# 04-Peripheral_Interface.net
KiCad netlist of a schematic drawn in Altium Designer
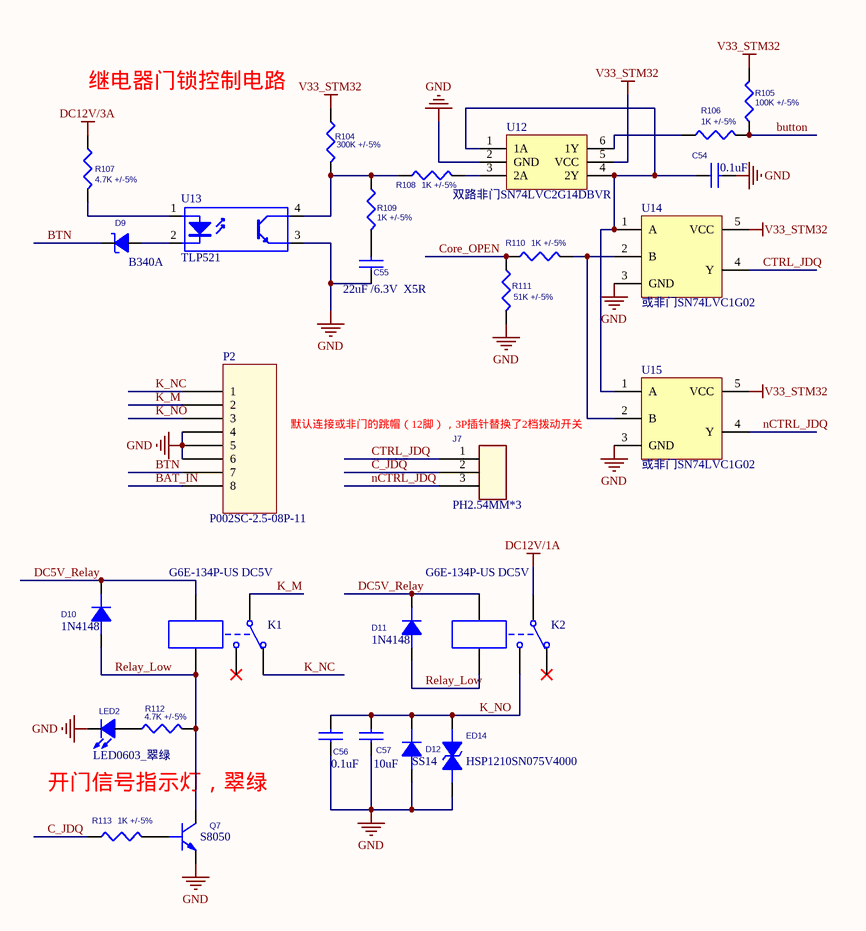
[diagram p0: 04-Peripheral Interface.SchDoc]

(export (version "E")
  (design (tool "Eeschema 10.0.6"))
  (components
    (comp (ref "C54")
      (value "0.1uF")
      (footprint "C0402")
      (description "表贴无极电容 0.1uF +10/-10% X7R")
      (libsource (lib "My_Library") (part "CAP"))
    )
    (comp (ref "C55")
      (value "22uF /6.3V  X5R")
      (footprint "C0805")
      (description "RoHS CHIP CAP 0.1uF +10/-10% X7R")
      (libsource (lib "My_Library") (part "CAP"))
    )
    (comp (ref "C56")
      (value "0.1uF")
      (footprint "C0402")
      (description "RoHS CHIP CAP 0.1uF +10/-10% X7R")
      (libsource (lib "My_Library") (part "CAP"))
    )
    (comp (ref "C57")
      (value "10uF")
      (footprint "C0603")
      (description "RoHS CHIP CAP 0.1uF +10/-10% X7R")
      (libsource (lib "My_Library") (part "CAP"))
    )
    (comp (ref "D9")
      (value "B340A")
      (footprint "DO-214AC/SMA")
      (description "RoHS 0.5A SURFACE MOUNT SCHOTTKY BARRIER RECTIFIER 1N5819")
      (libsource (lib "My_Library") (part "DIODE_Schottky-0"))
    )
    (comp (ref "D10")
      (value "1N4148")
      (footprint "SOD323")
      (description "RoHS 0.5A SURFACE MOUNT SCHOTTKY BARRIER RECTIFIER 1N5819")
      (libsource (lib "My_Library") (part "DIODE"))
    )
    (comp (ref "D11")
      (value "1N4148")
      (footprint "SOD323")
      (description "RoHS 0.5A SURFACE MOUNT SCHOTTKY BARRIER RECTIFIER 1N5819")
      (libsource (lib "My_Library") (part "DIODE"))
    )
    (comp (ref "D12")
      (value "SS14")
      (footprint "DO-214AA/SMB")
      (description "RoHS 0.5A SURFACE MOUNT SCHOTTKY BARRIER RECTIFIER 1N5819")
      (libsource (lib "My_Library") (part "DIODE"))
    )
    (comp (ref "ED14")
      (value "HSP1210SN075V4000")
      (footprint "ESD1210")
      (description "AEM科技（苏州）股份有限公司西南区成都办事处    销售主管：张莉  电话18030573868")
      (libsource (lib "My_Library") (part "ESD"))
    )
    (comp (ref "J7")
      (value "PH2.54MM*3")
      (footprint "CON3")
      (description "2.54mm单排插针，默认短接靠近或非门字样的1 2脚")
      (libsource (lib "My_Library") (part "CON3"))
    )
    (comp (ref "K1")
      (value "G6E-134P-US DC5V")
      (footprint "G6E134PUS")
      (description "https://item.taobao.com/item.htm?spm=a1z09.2.0.0.8b3ce33OERfgM&id=552384788811&_u=mb0qso78504")
      (fields (field (name "PUBLISHER") "Altium Limited"))
      (libsource (lib "My_Library") (part "Relay-SPDT"))
    )
    (comp (ref "K2")
      (value "G6E-134P-US DC5V")
      (footprint "G6E134PUS")
      (description "https://item.taobao.com/item.htm?spm=a1z09.2.0.0.8b3ce33OERfgM&id=552384788811&_u=mb0qso78504")
      (fields (field (name "PUBLISHER") "Altium Limited"))
      (libsource (lib "My_Library") (part "Relay-SPDT"))
    )
    (comp (ref "LED2")
      (value "LED0603_翠绿")
      (footprint "LED0603")
      (description "0603LED指示灯，颜色不同")
      (libsource (lib "My_Library") (part "LED"))
    )
    (comp (ref "P2")
      (value "P002SC-2.5-08P-11")
      (footprint "2EDGKD-2.5-8P")
      (description "门禁8P连接座，成都联益都电子有限公司，联系电话17780015645，邮箱lyconn107@163.com")
      (libsource (lib "My_Library") (part "2EDGKD-2.5-8P"))
    )
    (comp (ref "Q7") (value "S8050") (footprint "SOT23") (libsource (lib "My_Library") (part "NPN")))
    (comp (ref "R104") (value "300K +/-5%") (footprint "R0402") (libsource (lib "My_Library") (part "RES")))
    (comp (ref "R105") (value "100K +/-5%") (footprint "R0402") (libsource (lib "My_Library") (part "RES")))
    (comp (ref "R106") (value "1K +/-5%") (footprint "R0402") (libsource (lib "My_Library") (part "RES")))
    (comp (ref "R107") (value "4.7K +/-5%") (footprint "R0402") (libsource (lib "My_Library") (part "RES")))
    (comp (ref "R108") (value "1K +/-5%") (footprint "R0402") (libsource (lib "My_Library") (part "RES")))
    (comp (ref "R109") (value "1K +/-5%") (footprint "R0402") (libsource (lib "My_Library") (part "RES")))
    (comp (ref "R110") (value "1K +/-5%") (footprint "R0402") (libsource (lib "My_Library") (part "RES")))
    (comp (ref "R111") (value "51K +/-5%") (footprint "R0402") (libsource (lib "My_Library") (part "RES")))
    (comp (ref "R112") (value "4.7K +/-5%") (footprint "R0402") (libsource (lib "My_Library") (part "RES")))
    (comp (ref "R113") (value "1K +/-5%") (footprint "R0402") (libsource (lib "My_Library") (part "RES")))
    (comp (ref "U12")
      (value "双路非门SN74LVC2G14DBVR")
      (footprint "SOT23-6")
      (description "2路反相器    文晔集团    王忠凯，13823710380")
      (fields (field (name "DESIGNER") "Beyond@MXJ"))
      (libsource (lib "My_Library") (part "SN74LVC2G14DBVR"))
    )
    (comp (ref "U13")
      (value "TLP521")
      (footprint "SMD-4")
      (description "TLP521 SMD-4    安森美或者东芝品牌")
      (fields (field (name "DESIGNER") "BEYOND@MXJ"))
      (libsource (lib "My_Library") (part "TLP521"))
    )
    (comp (ref "U14")
      (value "或非门SN74LVC1G02")
      (footprint "SOT23-5")
      (description "单路 2 输入逻辑门    文晔集团    王忠凯，13823710380")
      (fields (field (name "DESIGNER") "Beyond@MXJ"))
      (libsource (lib "My_Library") (part "Single 2-input"))
    )
    (comp (ref "U15")
      (value "或非门SN74LVC1G02")
      (footprint "SOT23-5")
      (description "单路 2 输入逻辑门     文晔集团    王忠凯，13823710380")
      (fields (field (name "DESIGNER") "Beyond@MXJ"))
      (libsource (lib "My_Library") (part "Single 2-input"))
    )
  )
  (nets
    (net (code "1") (name "/BAT_IN") (class "Default")
      (node (ref "P2") (pin "8") (pinfunction "8_8") (pintype "passive"))
    )
    (net (code "2") (name "/BTN") (class "Default")
      (node (ref "D9") (pin "2") (pinfunction "K_2") (pintype "passive"))
      (node (ref "P2") (pin "7") (pinfunction "7_7") (pintype "passive"))
    )
    (net (code "3") (name "/CTRL_JDQ") (class "Default")
      (node (ref "J7") (pin "1") (pinfunction "1_1") (pintype "passive"))
      (node (ref "U14") (pin "4") (pinfunction "Y_4") (pintype "passive"))
    )
    (net (code "4") (name "/C_JDQ") (class "Default")
      (node (ref "J7") (pin "2") (pinfunction "2_2") (pintype "passive"))
      (node (ref "R113") (pin "1") (pinfunction "R1_1") (pintype "passive"))
    )
    (net (code "5") (name "/Core_OPEN") (class "Default")
      (node (ref "R110") (pin "1") (pinfunction "R1_1") (pintype "passive"))
      (node (ref "R111") (pin "1") (pinfunction "R1_1") (pintype "passive"))
    )
    (net (code "6") (name "/DC5V_Relay") (class "Default")
      (node (ref "D10") (pin "2") (pinfunction "K_2") (pintype "passive"))
      (node (ref "D11") (pin "2") (pinfunction "K_2") (pintype "passive"))
      (node (ref "K1") (pin "1") (pinfunction "1_1") (pintype "passive"))
      (node (ref "K2") (pin "1") (pinfunction "1_1") (pintype "passive"))
    )
    (net (code "7") (name "/K_M") (class "Default")
      (node (ref "K1") (pin "7") (pinfunction "7_7") (pintype "passive"))
      (node (ref "P2") (pin "2") (pinfunction "2_2") (pintype "passive"))
    )
    (net (code "8") (name "/K_NC") (class "Default")
      (node (ref "K1") (pin "10") (pinfunction "10_10") (pintype "passive"))
      (node (ref "P2") (pin "1") (pinfunction "1_1") (pintype "passive"))
    )
    (net (code "9") (name "/K_NO") (class "Default")
      (node (ref "C56") (pin "2") (pinfunction "2_2") (pintype "passive"))
      (node (ref "C57") (pin "2") (pinfunction "2_2") (pintype "passive"))
      (node (ref "D12") (pin "2") (pinfunction "K_2") (pintype "passive"))
      (node (ref "ED14") (pin "2") (pinfunction "2_2") (pintype "passive"))
      (node (ref "K2") (pin "12") (pinfunction "12_12") (pintype "passive"))
      (node (ref "P2") (pin "3") (pinfunction "3_3") (pintype "passive"))
    )
    (net (code "10") (name "/Relay_Low") (class "Default")
      (node (ref "D10") (pin "1") (pinfunction "A_1") (pintype "passive"))
      (node (ref "D11") (pin "1") (pinfunction "A_1") (pintype "passive"))
      (node (ref "K1") (pin "6") (pinfunction "6_6") (pintype "passive"))
      (node (ref "K2") (pin "6") (pinfunction "6_6") (pintype "passive"))
      (node (ref "Q7") (pin "3") (pinfunction "C_3") (pintype "passive"))
      (node (ref "R112") (pin "2") (pinfunction "R2_2") (pintype "passive"))
    )
    (net (code "11") (name "/button") (class "Default")
      (node (ref "R105") (pin "1") (pinfunction "R1_1") (pintype "passive"))
      (node (ref "R106") (pin "2") (pinfunction "R2_2") (pintype "passive"))
    )
    (net (code "12") (name "/nCTRL_JDQ") (class "Default")
      (node (ref "J7") (pin "3") (pinfunction "3_3") (pintype "passive"))
      (node (ref "U15") (pin "4") (pinfunction "Y_4") (pintype "passive"))
    )
    (net (code "13") (name "DC12V{slash}1A") (class "Default")
      (node (ref "K2") (pin "7") (pinfunction "7_7") (pintype "passive"))
    )
    (net (code "14") (name "DC12V{slash}3A") (class "Default")
      (node (ref "R107") (pin "1") (pinfunction "R1_1") (pintype "passive"))
    )
    (net (code "15") (name "GND") (class "Default")
      (node (ref "C54") (pin "2") (pinfunction "2_2") (pintype "passive"))
      (node (ref "C55") (pin "1") (pinfunction "1_1") (pintype "passive"))
      (node (ref "C56") (pin "1") (pinfunction "1_1") (pintype "passive"))
      (node (ref "C57") (pin "1") (pinfunction "1_1") (pintype "passive"))
      (node (ref "D12") (pin "1") (pinfunction "A_1") (pintype "passive"))
      (node (ref "ED14") (pin "1") (pinfunction "1_1") (pintype "passive"))
      (node (ref "LED2") (pin "1") (pinfunction "CATHODE_1") (pintype "passive"))
      (node (ref "P2") (pin "4") (pinfunction "4_4") (pintype "passive"))
      (node (ref "P2") (pin "5") (pinfunction "5_5") (pintype "passive"))
      (node (ref "P2") (pin "6") (pinfunction "6_6") (pintype "passive"))
      (node (ref "Q7") (pin "2") (pinfunction "E_2") (pintype "passive"))
      (node (ref "R111") (pin "2") (pinfunction "R2_2") (pintype "passive"))
      (node (ref "U12") (pin "2") (pinfunction "GND_2") (pintype "passive"))
      (node (ref "U13") (pin "3") (pinfunction "E_3") (pintype "passive"))
      (node (ref "U14") (pin "3") (pinfunction "GND_3") (pintype "passive"))
      (node (ref "U15") (pin "3") (pinfunction "GND_3") (pintype "passive"))
    )
    (net (code "16") (name "Net-(D9-A)") (class "Default")
      (node (ref "D9") (pin "1") (pinfunction "A_1") (pintype "passive"))
      (node (ref "U13") (pin "2") (pinfunction "K_2") (pintype "passive"))
    )
    (net (code "17") (name "Net-(LED2-ANODE)") (class "Default")
      (node (ref "LED2") (pin "2") (pinfunction "ANODE_2") (pintype "passive"))
      (node (ref "R112") (pin "1") (pinfunction "R1_1") (pintype "passive"))
    )
    (net (code "18") (name "Net-(Q7-B)") (class "Default")
      (node (ref "Q7") (pin "1") (pinfunction "B_1") (pintype "passive"))
      (node (ref "R113") (pin "2") (pinfunction "R2_2") (pintype "passive"))
    )
    (net (code "19") (name "Net-(R104-R2)") (class "Default")
      (node (ref "R104") (pin "2") (pinfunction "R2_2") (pintype "passive"))
      (node (ref "R108") (pin "1") (pinfunction "R1_1") (pintype "passive"))
      (node (ref "R109") (pin "1") (pinfunction "R1_1") (pintype "passive"))
      (node (ref "U13") (pin "4") (pinfunction "C_4") (pintype "passive"))
    )
    (net (code "20") (name "Net-(R106-R1)") (class "Default")
      (node (ref "R106") (pin "1") (pinfunction "R1_1") (pintype "passive"))
      (node (ref "U12") (pin "6") (pinfunction "1Y_6") (pintype "passive"))
    )
    (net (code "21") (name "Net-(R107-R2)") (class "Default")
      (node (ref "R107") (pin "2") (pinfunction "R2_2") (pintype "passive"))
      (node (ref "U13") (pin "1") (pinfunction "A_1") (pintype "passive"))
    )
    (net (code "22") (name "Net-(R108-R2)") (class "Default")
      (node (ref "R108") (pin "2") (pinfunction "R2_2") (pintype "passive"))
      (node (ref "U12") (pin "3") (pinfunction "2A_3") (pintype "passive"))
    )
    (net (code "23") (name "Net-(R109-R2)") (class "Default")
      (node (ref "C55") (pin "2") (pinfunction "2_2") (pintype "passive"))
      (node (ref "R109") (pin "2") (pinfunction "R2_2") (pintype "passive"))
    )
    (net (code "24") (name "Net-(R110-R2)") (class "Default")
      (node (ref "R110") (pin "2") (pinfunction "R2_2") (pintype "passive"))
      (node (ref "U14") (pin "2") (pinfunction "B_2") (pintype "passive"))
      (node (ref "U15") (pin "2") (pinfunction "B_2") (pintype "passive"))
    )
    (net (code "25") (name "Net-(U12-1A)") (class "Default")
      (node (ref "C54") (pin "1") (pinfunction "1_1") (pintype "passive"))
      (node (ref "U12") (pin "1") (pinfunction "1A_1") (pintype "passive"))
      (node (ref "U12") (pin "4") (pinfunction "2Y_4") (pintype "passive"))
      (node (ref "U14") (pin "1") (pinfunction "A_1") (pintype "passive"))
      (node (ref "U15") (pin "1") (pinfunction "A_1") (pintype "passive"))
    )
    (net (code "26") (name "V33_STM32") (class "Default")
      (node (ref "R104") (pin "1") (pinfunction "R1_1") (pintype "passive"))
      (node (ref "R105") (pin "2") (pinfunction "R2_2") (pintype "passive"))
      (node (ref "U12") (pin "5") (pinfunction "VCC_5") (pintype "passive"))
      (node (ref "U14") (pin "5") (pinfunction "VCC_5") (pintype "passive"))
      (node (ref "U15") (pin "5") (pinfunction "VCC_5") (pintype "passive"))
    )
    (net (code "27") (name "unconnected-(K1-Pad12)") (class "Default")
      (node (ref "K1") (pin "12") (pinfunction "12_12") (pintype "passive+no_connect"))
    )
    (net (code "28") (name "unconnected-(K2-Pad10)") (class "Default")
      (node (ref "K2") (pin "10") (pinfunction "10_10") (pintype "passive+no_connect"))
    )
  )
)
